# Sensors.net
KiCad netlist of a schematic drawn in Altium Designer
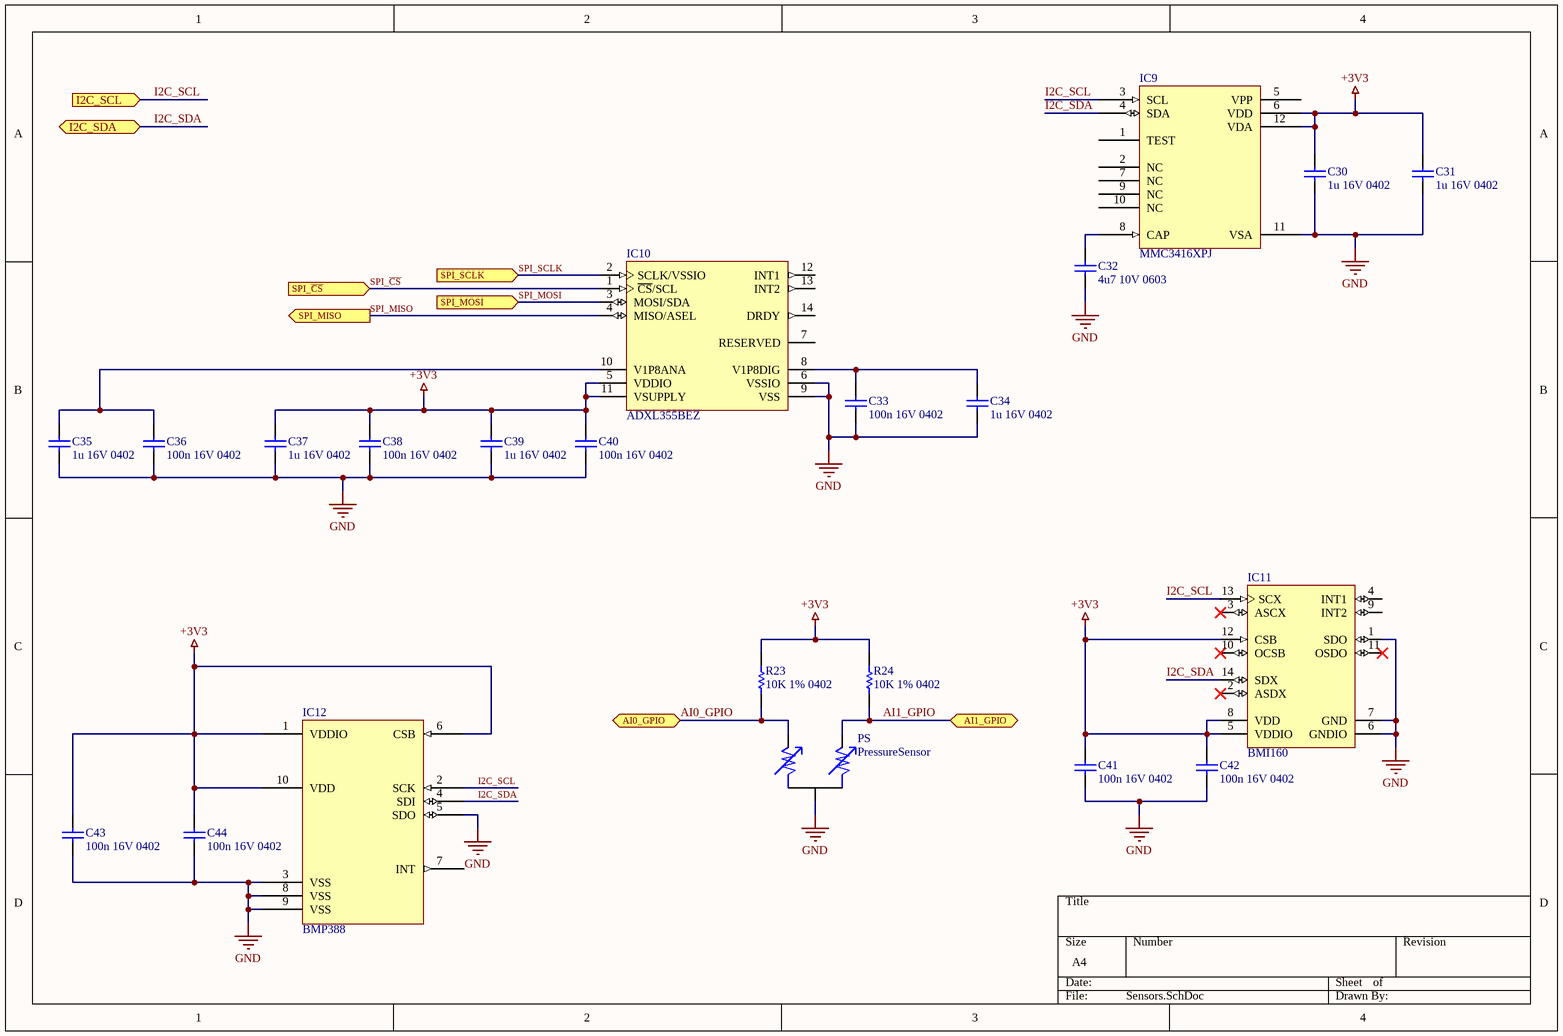
[diagram p0: Sensors.SchDoc]

(export (version "E")
  (design (tool "Eeschema 10.0.6"))
  (components
    (comp (ref "C30")
      (value "1u 16V 0402")
      (footprint "CAPC0402(1005)60_L")
      (description "CAP 1uF 16V ±10% 0402 (1005 Metric) Thickness 0.6mm SMD")
      (fields (field (name "TOLERANCE") "Â±10%"))
      (libsource (lib "Altium Content Vault") (part "CAP"))
    )
    (comp (ref "C31")
      (value "1u 16V 0402")
      (footprint "CAPC0402(1005)60_L")
      (description "CAP 1uF 16V ±10% 0402 (1005 Metric) Thickness 0.6mm SMD")
      (fields (field (name "TOLERANCE") "Â±10%"))
      (libsource (lib "Altium Content Vault") (part "CAP"))
    )
    (comp (ref "C32")
      (value "4u7 10V 0603")
      (footprint "CAPC0603(1608)100_L")
      (description "CAP 4.7uF 10V ±20% 0603 (1608 Metric) Thickness 1mm SMD")
      (fields (field (name "TOLERANCE") "Â±20%"))
      (libsource (lib "Altium Content Vault") (part "CAP"))
    )
    (comp (ref "C33")
      (value "100n 16V 0402")
      (footprint "CAPC0402(1005)60_L")
      (description "CAP 100nF 16V ±10% 0402 (1005 Metric) Thickness 0.6mm SMD")
      (fields (field (name "TOLERANCE") "Â±10%"))
      (libsource (lib "Altium Content Vault") (part "CAP"))
    )
    (comp (ref "C34")
      (value "1u 16V 0402")
      (footprint "CAPC0402(1005)60_L")
      (description "CAP 1uF 16V ±10% 0402 (1005 Metric) Thickness 0.6mm SMD")
      (fields (field (name "TOLERANCE") "Â±10%"))
      (libsource (lib "Altium Content Vault") (part "CAP"))
    )
    (comp (ref "C35")
      (value "1u 16V 0402")
      (footprint "CAPC0402(1005)60_L")
      (description "CAP 1uF 16V ±10% 0402 (1005 Metric) Thickness 0.6mm SMD")
      (fields (field (name "TOLERANCE") "Â±10%"))
      (libsource (lib "Altium Content Vault") (part "CAP"))
    )
    (comp (ref "C36")
      (value "100n 16V 0402")
      (footprint "CAPC0402(1005)60_L")
      (description "CAP 100nF 16V ±10% 0402 (1005 Metric) Thickness 0.6mm SMD")
      (fields (field (name "TOLERANCE") "Â±10%"))
      (libsource (lib "Altium Content Vault") (part "CAP"))
    )
    (comp (ref "C37")
      (value "1u 16V 0402")
      (footprint "CAPC0402(1005)60_L")
      (description "CAP 1uF 16V ±10% 0402 (1005 Metric) Thickness 0.6mm SMD")
      (fields (field (name "TOLERANCE") "Â±10%"))
      (libsource (lib "Altium Content Vault") (part "CAP"))
    )
    (comp (ref "C38")
      (value "100n 16V 0402")
      (footprint "CAPC0402(1005)60_L")
      (description "CAP 100nF 16V ±10% 0402 (1005 Metric) Thickness 0.6mm SMD")
      (fields (field (name "TOLERANCE") "Â±10%"))
      (libsource (lib "Altium Content Vault") (part "CAP"))
    )
    (comp (ref "C39")
      (value "1u 16V 0402")
      (footprint "CAPC0402(1005)60_L")
      (description "CAP 1uF 16V ±10% 0402 (1005 Metric) Thickness 0.6mm SMD")
      (fields (field (name "TOLERANCE") "Â±10%"))
      (libsource (lib "Altium Content Vault") (part "CAP"))
    )
    (comp (ref "C40")
      (value "100n 16V 0402")
      (footprint "CAPC0402(1005)60_L")
      (description "CAP 100nF 16V ±10% 0402 (1005 Metric) Thickness 0.6mm SMD")
      (fields (field (name "TOLERANCE") "Â±10%"))
      (libsource (lib "Altium Content Vault") (part "CAP"))
    )
    (comp (ref "C41")
      (value "100n 16V 0402")
      (footprint "CAPC0402(1005)60_L")
      (description "CAP 100nF 16V ±10% 0402 (1005 Metric) Thickness 0.6mm SMD")
      (fields (field (name "TOLERANCE") "Â±10%"))
      (libsource (lib "Altium Content Vault") (part "CAP"))
    )
    (comp (ref "C42")
      (value "100n 16V 0402")
      (footprint "CAPC0402(1005)60_L")
      (description "CAP 100nF 16V ±10% 0402 (1005 Metric) Thickness 0.6mm SMD")
      (fields (field (name "TOLERANCE") "Â±10%"))
      (libsource (lib "Altium Content Vault") (part "CAP"))
    )
    (comp (ref "C43")
      (value "100n 16V 0402")
      (footprint "CAPC0402(1005)60_L")
      (description "CAP 100nF 16V ±10% 0402 (1005 Metric) Thickness 0.6mm SMD")
      (fields (field (name "TOLERANCE") "Â±10%"))
      (libsource (lib "Altium Content Vault") (part "CAP"))
    )
    (comp (ref "C44")
      (value "100n 16V 0402")
      (footprint "CAPC0402(1005)60_L")
      (description "CAP 100nF 16V ±10% 0402 (1005 Metric) Thickness 0.6mm SMD")
      (fields (field (name "TOLERANCE") "Â±10%"))
      (libsource (lib "Altium Content Vault") (part "CAP"))
    )
    (comp (ref "IC9")
      (value "MMC3416XPJ")
      (footprint "BGA12C40P4X4_160X160X72")
      (libsource (lib "bleimuv6_intlib") (part "MMC3416XPJ"))
    )
    (comp (ref "IC10")
      (value "ADXL355BEZ")
      (footprint "ADI-ADXL355-LCC-14_V")
      (fields (field (name "MANUFACTURER") "Analog Devices"))
      (libsource (lib "Altium Content Vault") (part "ADI-ADXL355-LCC-14"))
    )
    (comp (ref "IC11")
      (value "BMI160")
      (footprint "BOSC-BMI160_V")
      (fields (field (name "MANUFACTURER") "Bosch"))
      (libsource (lib "Altium Content Vault") (part "BOSC-BMI160-LGA-14"))
    )
    (comp (ref "IC12")
      (value "BMP388")
      (footprint "BMP388")
      (libsource (lib "bleimuv6_intlib") (part "BMP388"))
    )
    (comp (ref "PS")
      (value "PressureSensor")
      (footprint "PressureSensor")
      (libsource (lib "bleimuv6_schlib") (part "PressureSensor"))
    )
    (comp (ref "R23")
      (value "10K 1% 0402")
      (footprint "RESC0402(1005)_L")
      (description "10K 0.063W 1% 0402 (1005 Metric)  SMD")
      (fields (field (name "TOLERANCE") "1 %") (field (name "POWER") "0.063 W"))
      (libsource (lib "Altium Content Vault") (part "RES"))
    )
    (comp (ref "R24")
      (value "10K 1% 0402")
      (footprint "RESC0402(1005)_L")
      (description "10K 0.063W 1% 0402 (1005 Metric)  SMD")
      (fields (field (name "TOLERANCE") "1 %") (field (name "POWER") "0.063 W"))
      (libsource (lib "Altium Content Vault") (part "RES"))
    )
  )
  (nets
    (net (code "1") (name "+3V3") (class "Default")
      (node (ref "C30") (pin "1") (pinfunction "1_1") (pintype "passive"))
      (node (ref "C31") (pin "1") (pinfunction "1_1") (pintype "passive"))
      (node (ref "C37") (pin "1") (pinfunction "1_1") (pintype "passive"))
      (node (ref "C38") (pin "2") (pinfunction "2_2") (pintype "passive"))
      (node (ref "C39") (pin "1") (pinfunction "1_1") (pintype "passive"))
      (node (ref "C40") (pin "2") (pinfunction "2_2") (pintype "passive"))
      (node (ref "C41") (pin "2") (pinfunction "2_2") (pintype "passive"))
      (node (ref "C42") (pin "2") (pinfunction "2_2") (pintype "passive"))
      (node (ref "C43") (pin "2") (pinfunction "2_2") (pintype "passive"))
      (node (ref "C44") (pin "2") (pinfunction "2_2") (pintype "passive"))
      (node (ref "IC10") (pin "11") (pinfunction "VSUPPLY_11") (pintype "power_in"))
      (node (ref "IC10") (pin "5") (pinfunction "VDDIO_5") (pintype "power_in"))
      (node (ref "IC11") (pin "12") (pinfunction "CSB_12") (pintype "input"))
      (node (ref "IC11") (pin "5") (pinfunction "VDDIO_5") (pintype "power_in"))
      (node (ref "IC11") (pin "8") (pinfunction "VDD_8") (pintype "power_in"))
      (node (ref "IC12") (pin "1") (pinfunction "VDDIO_1") (pintype "power_in"))
      (node (ref "IC12") (pin "10") (pinfunction "VDD_10") (pintype "power_in"))
      (node (ref "IC12") (pin "6") (pinfunction "CSB_6") (pintype "input"))
      (node (ref "IC9") (pin "12") (pinfunction "VDA_12") (pintype "power_in"))
      (node (ref "IC9") (pin "6") (pinfunction "VDD_6") (pintype "power_in"))
      (node (ref "R23") (pin "2") (pinfunction "2_2") (pintype "passive"))
      (node (ref "R24") (pin "2") (pinfunction "2_2") (pintype "passive"))
    )
    (net (code "2") (name "/AI0_GPIO") (class "Default")
      (node (ref "PS") (pin "3") (pinfunction "3_3") (pintype "passive"))
      (node (ref "R23") (pin "1") (pinfunction "1_1") (pintype "passive"))
    )
    (net (code "3") (name "/AI1_GPIO") (class "Default")
      (node (ref "PS") (pin "2") (pinfunction "2_2") (pintype "passive"))
      (node (ref "R24") (pin "1") (pinfunction "1_1") (pintype "passive"))
    )
    (net (code "4") (name "/I2C_SCL") (class "Default")
      (node (ref "IC11") (pin "13") (pinfunction "SCX_13") (pintype "input"))
      (node (ref "IC12") (pin "2") (pinfunction "SCK_2") (pintype "input"))
      (node (ref "IC9") (pin "3") (pinfunction "SCL_3") (pintype "input"))
    )
    (net (code "5") (name "/I2C_SDA") (class "Default")
      (node (ref "IC11") (pin "14") (pinfunction "SDX_14") (pintype "bidirectional"))
      (node (ref "IC12") (pin "4") (pinfunction "SDI_4") (pintype "bidirectional"))
      (node (ref "IC9") (pin "4") (pinfunction "SDA_4") (pintype "bidirectional"))
    )
    (net (code "6") (name "/SPI_MISO") (class "Default")
      (node (ref "IC10") (pin "4") (pinfunction "MISO/ASEL_4") (pintype "bidirectional"))
    )
    (net (code "7") (name "/SPI_MOSI") (class "Default")
      (node (ref "IC10") (pin "3") (pinfunction "MOSI/SDA_3") (pintype "bidirectional"))
    )
    (net (code "8") (name "/SPI_SCLK") (class "Default")
      (node (ref "IC10") (pin "2") (pinfunction "SCLK/VSSIO_2") (pintype "input"))
    )
    (net (code "9") (name "/SPI_~{CS}") (class "Default")
      (node (ref "IC10") (pin "1") (pinfunction "~{CS}/SCL_1") (pintype "input"))
    )
    (net (code "10") (name "GND") (class "Default")
      (node (ref "C30") (pin "2") (pinfunction "2_2") (pintype "passive"))
      (node (ref "C31") (pin "2") (pinfunction "2_2") (pintype "passive"))
      (node (ref "C32") (pin "1") (pinfunction "1_1") (pintype "passive"))
      (node (ref "C33") (pin "1") (pinfunction "1_1") (pintype "passive"))
      (node (ref "C34") (pin "2") (pinfunction "2_2") (pintype "passive"))
      (node (ref "C35") (pin "2") (pinfunction "2_2") (pintype "passive"))
      (node (ref "C36") (pin "1") (pinfunction "1_1") (pintype "passive"))
      (node (ref "C37") (pin "2") (pinfunction "2_2") (pintype "passive"))
      (node (ref "C38") (pin "1") (pinfunction "1_1") (pintype "passive"))
      (node (ref "C39") (pin "2") (pinfunction "2_2") (pintype "passive"))
      (node (ref "C40") (pin "1") (pinfunction "1_1") (pintype "passive"))
      (node (ref "C41") (pin "1") (pinfunction "1_1") (pintype "passive"))
      (node (ref "C42") (pin "1") (pinfunction "1_1") (pintype "passive"))
      (node (ref "C43") (pin "1") (pinfunction "1_1") (pintype "passive"))
      (node (ref "C44") (pin "1") (pinfunction "1_1") (pintype "passive"))
      (node (ref "IC10") (pin "6") (pinfunction "VSSIO_6") (pintype "power_in"))
      (node (ref "IC10") (pin "9") (pinfunction "VSS_9") (pintype "power_in"))
      (node (ref "IC11") (pin "1") (pinfunction "SDO_1") (pintype "bidirectional"))
      (node (ref "IC11") (pin "6") (pinfunction "GNDIO_6") (pintype "power_in"))
      (node (ref "IC11") (pin "7") (pinfunction "GND_7") (pintype "power_in"))
      (node (ref "IC12") (pin "3") (pinfunction "VSS_3") (pintype "power_in"))
      (node (ref "IC12") (pin "5") (pinfunction "SDO_5") (pintype "bidirectional"))
      (node (ref "IC12") (pin "8") (pinfunction "VSS_8") (pintype "power_in"))
      (node (ref "IC12") (pin "9") (pinfunction "VSS_9") (pintype "power_in"))
      (node (ref "IC9") (pin "11") (pinfunction "VSA_11") (pintype "power_in"))
      (node (ref "PS") (pin "1") (pinfunction "24_1") (pintype "passive"))
    )
    (net (code "11") (name "Net-(IC9-CAP)") (class "Default")
      (node (ref "C32") (pin "2") (pinfunction "2_2") (pintype "passive"))
      (node (ref "IC9") (pin "8") (pinfunction "CAP_8") (pintype "input"))
    )
    (net (code "12") (name "Net-(IC10-V1P8ANA)") (class "Default")
      (node (ref "C35") (pin "1") (pinfunction "1_1") (pintype "passive"))
      (node (ref "C36") (pin "2") (pinfunction "2_2") (pintype "passive"))
      (node (ref "IC10") (pin "10") (pinfunction "V1P8ANA_10") (pintype "power_in"))
    )
    (net (code "13") (name "Net-(IC10-V1P8DIG)") (class "Default")
      (node (ref "C33") (pin "2") (pinfunction "2_2") (pintype "passive"))
      (node (ref "C34") (pin "1") (pinfunction "1_1") (pintype "passive"))
      (node (ref "IC10") (pin "8") (pinfunction "V1P8DIG_8") (pintype "power_in"))
    )
    (net (code "14") (name "unconnected-(IC9-NC-Pad2)") (class "Default")
      (node (ref "IC9") (pin "2") (pinfunction "NC_2") (pintype "passive"))
    )
    (net (code "15") (name "unconnected-(IC9-NC-Pad7)") (class "Default")
      (node (ref "IC9") (pin "7") (pinfunction "NC_7") (pintype "passive"))
    )
    (net (code "16") (name "unconnected-(IC9-NC-Pad9)") (class "Default")
      (node (ref "IC9") (pin "9") (pinfunction "NC_9") (pintype "passive"))
    )
    (net (code "17") (name "unconnected-(IC9-NC-Pad10)") (class "Default")
      (node (ref "IC9") (pin "10") (pinfunction "NC_10") (pintype "passive"))
    )
    (net (code "18") (name "unconnected-(IC9-TEST-Pad1)") (class "Default")
      (node (ref "IC9") (pin "1") (pinfunction "TEST_1") (pintype "passive"))
    )
    (net (code "19") (name "unconnected-(IC9-VPP-Pad5)") (class "Default")
      (node (ref "IC9") (pin "5") (pinfunction "VPP_5") (pintype "passive"))
    )
    (net (code "20") (name "unconnected-(IC10-DRDY-Pad14)") (class "Default")
      (node (ref "IC10") (pin "14") (pinfunction "DRDY_14") (pintype "output"))
    )
    (net (code "21") (name "unconnected-(IC10-INT1-Pad12)") (class "Default")
      (node (ref "IC10") (pin "12") (pinfunction "INT1_12") (pintype "output"))
    )
    (net (code "22") (name "unconnected-(IC10-INT2-Pad13)") (class "Default")
      (node (ref "IC10") (pin "13") (pinfunction "INT2_13") (pintype "output"))
    )
    (net (code "23") (name "unconnected-(IC10-RESERVED-Pad7)") (class "Default")
      (node (ref "IC10") (pin "7") (pinfunction "RESERVED_7") (pintype "passive"))
    )
    (net (code "24") (name "unconnected-(IC11-ASCX-Pad3)") (class "Default")
      (node (ref "IC11") (pin "3") (pinfunction "ASCX_3") (pintype "bidirectional+no_connect"))
    )
    (net (code "25") (name "unconnected-(IC11-ASDX-Pad2)") (class "Default")
      (node (ref "IC11") (pin "2") (pinfunction "ASDX_2") (pintype "bidirectional+no_connect"))
    )
    (net (code "26") (name "unconnected-(IC11-INT1-Pad4)") (class "Default")
      (node (ref "IC11") (pin "4") (pinfunction "INT1_4") (pintype "bidirectional"))
    )
    (net (code "27") (name "unconnected-(IC11-INT2-Pad9)") (class "Default")
      (node (ref "IC11") (pin "9") (pinfunction "INT2_9") (pintype "bidirectional"))
    )
    (net (code "28") (name "unconnected-(IC11-OCSB-Pad10)") (class "Default")
      (node (ref "IC11") (pin "10") (pinfunction "OCSB_10") (pintype "bidirectional+no_connect"))
    )
    (net (code "29") (name "unconnected-(IC11-OSDO-Pad11)") (class "Default")
      (node (ref "IC11") (pin "11") (pinfunction "OSDO_11") (pintype "bidirectional+no_connect"))
    )
    (net (code "30") (name "unconnected-(IC12-INT-Pad7)") (class "Default")
      (node (ref "IC12") (pin "7") (pinfunction "INT_7") (pintype "output"))
    )
  )
)
